# 0101.net
KiCad netlist of a schematic drawn in EAGLE
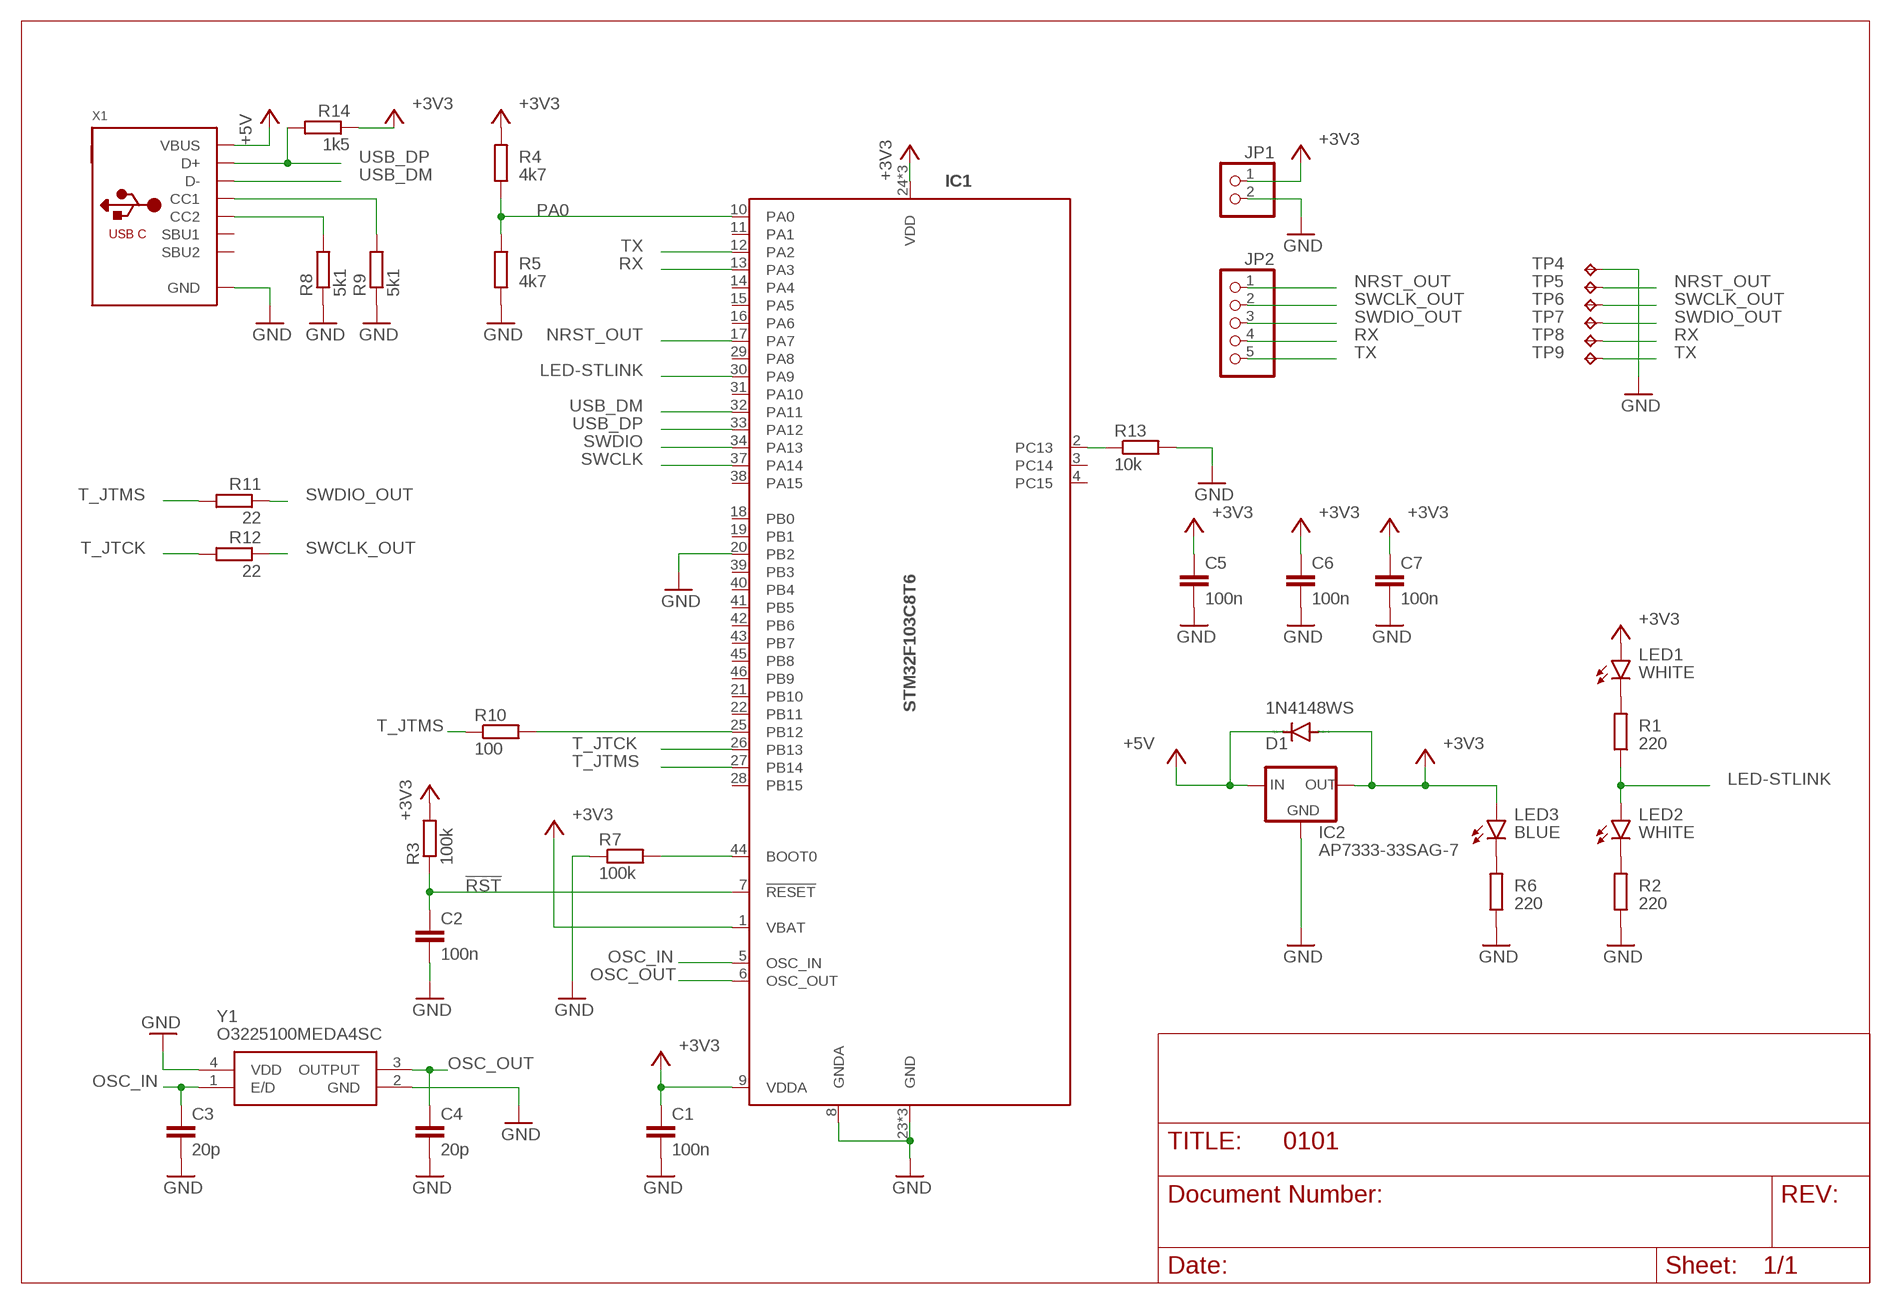
[diagram p0: schematic, sheet 1]

(export (version "E")
  (design (tool "Eeschema 10.0.6"))
  (components
    (comp (ref "C1")
      (value "100n")
      (footprint "eagle-import:C0402")
      (libsource (lib "eagle-import") (part "C-EUC0402"))
    )
    (comp (ref "C2")
      (value "100n")
      (footprint "eagle-import:C0402")
      (libsource (lib "eagle-import") (part "C-EUC0402"))
    )
    (comp (ref "C3")
      (value "20p")
      (footprint "eagle-import:C0402")
      (libsource (lib "eagle-import") (part "C-EUC0402"))
    )
    (comp (ref "C4")
      (value "20p")
      (footprint "eagle-import:C0402")
      (libsource (lib "eagle-import") (part "C-EUC0402"))
    )
    (comp (ref "C5")
      (value "100n")
      (footprint "eagle-import:C0402")
      (libsource (lib "eagle-import") (part "C-EUC0402"))
    )
    (comp (ref "C6")
      (value "100n")
      (footprint "eagle-import:C0402")
      (libsource (lib "eagle-import") (part "C-EUC0402"))
    )
    (comp (ref "C7")
      (value "100n")
      (footprint "eagle-import:C0402")
      (libsource (lib "eagle-import") (part "C-EUC0402"))
    )
    (comp (ref "D1")
      (value "1N4148WS")
      (footprint "eagle-import:SOD323-R")
      (libsource (lib "eagle-import") (part "DIODE-SOD323-R"))
    )
    (comp (ref "IC1")
      (value "STM32F103C8T6")
      (footprint "eagle-import:QFP48-7X7-0.5")
      (fields (field (name "MF") "ST"))
      (libsource (lib "eagle-import") (part "STM32F103CT68"))
    )
    (comp (ref "IC2")
      (value "AP7333-33SAG-7")
      (footprint "eagle-import:SOT23")
      (libsource (lib "eagle-import") (part "XC63FPM"))
    )
    (comp (ref "JP1")
      (value "PINHD-1X2")
      (footprint "eagle-import:1X02")
      (libsource (lib "eagle-import") (part "PINHD-1X2"))
    )
    (comp (ref "JP2")
      (value "PINHD-1X5")
      (footprint "eagle-import:1X05")
      (libsource (lib "eagle-import") (part "PINHD-1X5"))
    )
    (comp (ref "LED1")
      (value "WHITE")
      (footprint "eagle-import:CHIP-LED0603")
      (libsource (lib "eagle-import") (part "LEDCHIP-LED0603"))
    )
    (comp (ref "LED2")
      (value "WHITE")
      (footprint "eagle-import:CHIP-LED0603")
      (libsource (lib "eagle-import") (part "LEDCHIP-LED0603"))
    )
    (comp (ref "LED3")
      (value "BLUE")
      (footprint "eagle-import:CHIP-LED0603")
      (libsource (lib "eagle-import") (part "LEDCHIP-LED0603"))
    )
    (comp (ref "R1")
      (value "220")
      (footprint "eagle-import:R0402")
      (libsource (lib "eagle-import") (part "R-EU_R0402"))
    )
    (comp (ref "R2")
      (value "220")
      (footprint "eagle-import:R0402")
      (libsource (lib "eagle-import") (part "R-EU_R0402"))
    )
    (comp (ref "R3")
      (value "100k")
      (footprint "eagle-import:R0402")
      (libsource (lib "eagle-import") (part "R-EU_R0402"))
    )
    (comp (ref "R4")
      (value "4k7")
      (footprint "eagle-import:R0402")
      (libsource (lib "eagle-import") (part "R-EU_R0402"))
    )
    (comp (ref "R5")
      (value "4k7")
      (footprint "eagle-import:R0402")
      (libsource (lib "eagle-import") (part "R-EU_R0402"))
    )
    (comp (ref "R6")
      (value "220")
      (footprint "eagle-import:R0402")
      (libsource (lib "eagle-import") (part "R-EU_R0402"))
    )
    (comp (ref "R7")
      (value "100k")
      (footprint "eagle-import:R0402")
      (libsource (lib "eagle-import") (part "R-EU_R0402"))
    )
    (comp (ref "R8")
      (value "5k1")
      (footprint "eagle-import:R0402")
      (libsource (lib "eagle-import") (part "R-EU_R0402"))
    )
    (comp (ref "R9")
      (value "5k1")
      (footprint "eagle-import:R0402")
      (libsource (lib "eagle-import") (part "R-EU_R0402"))
    )
    (comp (ref "R10")
      (value "100")
      (footprint "eagle-import:R0402")
      (libsource (lib "eagle-import") (part "R-EU_R0402"))
    )
    (comp (ref "R11")
      (value "22")
      (footprint "eagle-import:R0402")
      (libsource (lib "eagle-import") (part "R-EU_R0402"))
    )
    (comp (ref "R12")
      (value "22")
      (footprint "eagle-import:R0402")
      (libsource (lib "eagle-import") (part "R-EU_R0402"))
    )
    (comp (ref "R13")
      (value "10k")
      (footprint "eagle-import:R0402")
      (libsource (lib "eagle-import") (part "R-EU_R0402"))
    )
    (comp (ref "R14")
      (value "1k5")
      (footprint "eagle-import:R0402")
      (libsource (lib "eagle-import") (part "R-EU_R0402"))
    )
    (comp (ref "TP4")
      (value "TPTP10SQ")
      (footprint "eagle-import:TP10SQ")
      (libsource (lib "eagle-import") (part "TPTP10SQ"))
    )
    (comp (ref "TP5")
      (value "TPTP10R")
      (footprint "eagle-import:TP10R")
      (libsource (lib "eagle-import") (part "TPTP10R"))
    )
    (comp (ref "TP6")
      (value "TPTP10R")
      (footprint "eagle-import:TP10R")
      (libsource (lib "eagle-import") (part "TPTP10R"))
    )
    (comp (ref "TP7")
      (value "TPTP10R")
      (footprint "eagle-import:TP10R")
      (libsource (lib "eagle-import") (part "TPTP10R"))
    )
    (comp (ref "TP8")
      (value "TPTP10R")
      (footprint "eagle-import:TP10R")
      (libsource (lib "eagle-import") (part "TPTP10R"))
    )
    (comp (ref "TP9")
      (value "TPTP10R")
      (footprint "eagle-import:TP10R")
      (libsource (lib "eagle-import") (part "TPTP10R"))
    )
    (comp (ref "X1")
      (value "USB_C")
      (footprint "eagle-import:USB_C_CUSB31-CFM2AX-01-X")
      (libsource (lib "eagle-import") (part "USB_C"))
    )
    (comp (ref "Y1")
      (value "O3225100MEDA4SC")
      (footprint "eagle-import:O3225100MEDA4SC")
      (libsource (lib "eagle-import") (part "O3225100MEDA4SC"))
    )
  )
  (nets
    (net (code "1") (name "+3V3") (class "Default")
      (node (ref "C1") (pin "1") (pinfunction "1_1") (pintype "passive"))
      (node (ref "C5") (pin "1") (pinfunction "1_1") (pintype "passive"))
      (node (ref "C6") (pin "1") (pinfunction "1_1") (pintype "passive"))
      (node (ref "C7") (pin "1") (pinfunction "1_1") (pintype "passive"))
      (node (ref "D1") (pin "A") (pinfunction "A_A") (pintype "passive"))
      (node (ref "IC1") (pin "1") (pinfunction "VBAT_1") (pintype "power_in"))
      (node (ref "IC1") (pin "24") (pinfunction "VDD_24") (pintype "power_in"))
      (node (ref "IC1") (pin "36") (pinfunction "VDD_36") (pintype "power_in"))
      (node (ref "IC1") (pin "48") (pinfunction "VDD_48") (pintype "power_in"))
      (node (ref "IC1") (pin "9") (pinfunction "VDDA_9") (pintype "input"))
      (node (ref "IC2") (pin "2") (pinfunction "OUT_2") (pintype "passive"))
      (node (ref "JP1") (pin "1") (pinfunction "1_1") (pintype "passive"))
      (node (ref "LED1") (pin "A") (pinfunction "A_A") (pintype "passive"))
      (node (ref "LED3") (pin "A") (pinfunction "A_A") (pintype "passive"))
      (node (ref "R14") (pin "1") (pinfunction "1_1") (pintype "passive"))
      (node (ref "R3") (pin "2") (pinfunction "2_2") (pintype "passive"))
      (node (ref "R4") (pin "2") (pinfunction "2_2") (pintype "passive"))
    )
    (net (code "2") (name "+5V") (class "Default")
      (node (ref "D1") (pin "C") (pinfunction "C_C") (pintype "passive"))
      (node (ref "IC2") (pin "3") (pinfunction "IN_3") (pintype "input"))
      (node (ref "X1") (pin "A4B9") (pinfunction "VBUS_A4B9") (pintype "power_in"))
      (node (ref "X1") (pin "B4A9") (pinfunction "VBUS_B4A9") (pintype "power_in"))
    )
    (net (code "3") (name "/LED-STLINK") (class "Default")
      (node (ref "IC1") (pin "30") (pinfunction "PA9_30") (pintype "bidirectional"))
      (node (ref "LED2") (pin "A") (pinfunction "A_A") (pintype "passive"))
      (node (ref "R1") (pin "1") (pinfunction "1_1") (pintype "passive"))
    )
    (net (code "4") (name "/NRST_OUT") (class "Default")
      (node (ref "IC1") (pin "17") (pinfunction "PA7_17") (pintype "bidirectional"))
      (node (ref "JP2") (pin "1") (pinfunction "1_1") (pintype "passive"))
      (node (ref "TP5") (pin "TP") (pinfunction "TP_TP") (pintype "input"))
    )
    (net (code "5") (name "/OSC_IN") (class "Default")
      (node (ref "C3") (pin "1") (pinfunction "1_1") (pintype "passive"))
      (node (ref "IC1") (pin "5") (pinfunction "OSC_IN_5") (pintype "input"))
      (node (ref "Y1") (pin "1") (pinfunction "E/D_1") (pintype "bidirectional"))
    )
    (net (code "6") (name "/OSC_OUT") (class "Default")
      (node (ref "C4") (pin "1") (pinfunction "1_1") (pintype "passive"))
      (node (ref "IC1") (pin "6") (pinfunction "OSC_OUT_6") (pintype "output"))
      (node (ref "Y1") (pin "3") (pinfunction "OUTPUT_3") (pintype "bidirectional"))
    )
    (net (code "7") (name "/PA0") (class "Default")
      (node (ref "IC1") (pin "10") (pinfunction "PA0_10") (pintype "bidirectional"))
      (node (ref "R4") (pin "1") (pinfunction "1_1") (pintype "passive"))
      (node (ref "R5") (pin "2") (pinfunction "2_2") (pintype "passive"))
    )
    (net (code "8") (name "/RX") (class "Default")
      (node (ref "IC1") (pin "13") (pinfunction "PA3_13") (pintype "bidirectional"))
      (node (ref "JP2") (pin "4") (pinfunction "4_4") (pintype "passive"))
      (node (ref "TP8") (pin "TP") (pinfunction "TP_TP") (pintype "input"))
    )
    (net (code "9") (name "/SWCLK") (class "Default")
      (node (ref "IC1") (pin "37") (pinfunction "PA14_37") (pintype "bidirectional"))
    )
    (net (code "10") (name "/SWCLK_OUT") (class "Default")
      (node (ref "JP2") (pin "2") (pinfunction "2_2") (pintype "passive"))
      (node (ref "R12") (pin "1") (pinfunction "1_1") (pintype "passive"))
      (node (ref "TP6") (pin "TP") (pinfunction "TP_TP") (pintype "input"))
    )
    (net (code "11") (name "/SWDIO") (class "Default")
      (node (ref "IC1") (pin "34") (pinfunction "PA13_34") (pintype "bidirectional"))
    )
    (net (code "12") (name "/SWDIO_OUT") (class "Default")
      (node (ref "JP2") (pin "3") (pinfunction "3_3") (pintype "passive"))
      (node (ref "R11") (pin "1") (pinfunction "1_1") (pintype "passive"))
      (node (ref "TP7") (pin "TP") (pinfunction "TP_TP") (pintype "input"))
    )
    (net (code "13") (name "/TX") (class "Default")
      (node (ref "IC1") (pin "12") (pinfunction "PA2_12") (pintype "bidirectional"))
      (node (ref "JP2") (pin "5") (pinfunction "5_5") (pintype "passive"))
      (node (ref "TP9") (pin "TP") (pinfunction "TP_TP") (pintype "input"))
    )
    (net (code "14") (name "/T_JTCK") (class "Default")
      (node (ref "IC1") (pin "26") (pinfunction "PB13_26") (pintype "bidirectional"))
      (node (ref "R12") (pin "2") (pinfunction "2_2") (pintype "passive"))
    )
    (net (code "15") (name "/T_JTMS") (class "Default")
      (node (ref "IC1") (pin "27") (pinfunction "PB14_27") (pintype "bidirectional"))
      (node (ref "R10") (pin "1") (pinfunction "1_1") (pintype "passive"))
      (node (ref "R11") (pin "2") (pinfunction "2_2") (pintype "passive"))
    )
    (net (code "16") (name "/USB_DM") (class "Default")
      (node (ref "IC1") (pin "32") (pinfunction "PA11_32") (pintype "bidirectional"))
      (node (ref "X1") (pin "A7") (pinfunction "D-_A7") (pintype "bidirectional"))
      (node (ref "X1") (pin "B7") (pinfunction "D-_B7") (pintype "bidirectional"))
    )
    (net (code "17") (name "/USB_DP") (class "Default")
      (node (ref "IC1") (pin "33") (pinfunction "PA12_33") (pintype "bidirectional"))
      (node (ref "R14") (pin "2") (pinfunction "2_2") (pintype "passive"))
      (node (ref "X1") (pin "A6") (pinfunction "D+_A6") (pintype "bidirectional"))
      (node (ref "X1") (pin "B6") (pinfunction "D+_B6") (pintype "bidirectional"))
    )
    (net (code "18") (name "/~{RST}") (class "Default")
      (node (ref "C2") (pin "1") (pinfunction "1_1") (pintype "passive"))
      (node (ref "IC1") (pin "7") (pinfunction "~{RESET}_7") (pintype "input"))
      (node (ref "R3") (pin "1") (pinfunction "1_1") (pintype "passive"))
    )
    (net (code "19") (name "GND") (class "Default")
      (node (ref "C1") (pin "2") (pinfunction "2_2") (pintype "passive"))
      (node (ref "C2") (pin "2") (pinfunction "2_2") (pintype "passive"))
      (node (ref "C3") (pin "2") (pinfunction "2_2") (pintype "passive"))
      (node (ref "C4") (pin "2") (pinfunction "2_2") (pintype "passive"))
      (node (ref "C5") (pin "2") (pinfunction "2_2") (pintype "passive"))
      (node (ref "C6") (pin "2") (pinfunction "2_2") (pintype "passive"))
      (node (ref "C7") (pin "2") (pinfunction "2_2") (pintype "passive"))
      (node (ref "IC1") (pin "20") (pinfunction "PB2_20") (pintype "bidirectional"))
      (node (ref "IC1") (pin "23") (pinfunction "GND_23") (pintype "power_in"))
      (node (ref "IC1") (pin "35") (pinfunction "GND_35") (pintype "power_in"))
      (node (ref "IC1") (pin "47") (pinfunction "GND_47") (pintype "power_in"))
      (node (ref "IC1") (pin "8") (pinfunction "GNDA_8") (pintype "bidirectional"))
      (node (ref "IC2") (pin "1") (pinfunction "GND_1") (pintype "input"))
      (node (ref "JP1") (pin "2") (pinfunction "2_2") (pintype "passive"))
      (node (ref "R13") (pin "2") (pinfunction "2_2") (pintype "passive"))
      (node (ref "R2") (pin "1") (pinfunction "1_1") (pintype "passive"))
      (node (ref "R5") (pin "1") (pinfunction "1_1") (pintype "passive"))
      (node (ref "R6") (pin "1") (pinfunction "1_1") (pintype "passive"))
      (node (ref "R7") (pin "1") (pinfunction "1_1") (pintype "passive"))
      (node (ref "R8") (pin "1") (pinfunction "1_1") (pintype "passive"))
      (node (ref "R9") (pin "1") (pinfunction "1_1") (pintype "passive"))
      (node (ref "TP4") (pin "TP") (pinfunction "TP_TP") (pintype "input"))
      (node (ref "X1") (pin "A1B12") (pinfunction "GND_A1B12") (pintype "power_in"))
      (node (ref "X1") (pin "B1A12") (pinfunction "GND_B1A12") (pintype "power_in"))
      (node (ref "Y1") (pin "2") (pinfunction "GND_2") (pintype "bidirectional"))
      (node (ref "Y1") (pin "4") (pinfunction "VDD_4") (pintype "bidirectional"))
    )
    (net (code "20") (name "Net-(IC1-BOOT0)") (class "Default")
      (node (ref "IC1") (pin "44") (pinfunction "BOOT0_44") (pintype "input"))
      (node (ref "R7") (pin "2") (pinfunction "2_2") (pintype "passive"))
    )
    (net (code "21") (name "Net-(IC1-PB12)") (class "Default")
      (node (ref "IC1") (pin "25") (pinfunction "PB12_25") (pintype "bidirectional"))
      (node (ref "R10") (pin "2") (pinfunction "2_2") (pintype "passive"))
    )
    (net (code "22") (name "Net-(IC1-PC13)") (class "Default")
      (node (ref "IC1") (pin "2") (pinfunction "PC13_2") (pintype "bidirectional"))
      (node (ref "R13") (pin "1") (pinfunction "1_1") (pintype "passive"))
    )
    (net (code "23") (name "Net-(LED1-PadC)") (class "Default")
      (node (ref "LED1") (pin "C") (pinfunction "C_C") (pintype "passive"))
      (node (ref "R1") (pin "2") (pinfunction "2_2") (pintype "passive"))
    )
    (net (code "24") (name "Net-(LED2-PadC)") (class "Default")
      (node (ref "LED2") (pin "C") (pinfunction "C_C") (pintype "passive"))
      (node (ref "R2") (pin "2") (pinfunction "2_2") (pintype "passive"))
    )
    (net (code "25") (name "Net-(LED3-PadC)") (class "Default")
      (node (ref "LED3") (pin "C") (pinfunction "C_C") (pintype "passive"))
      (node (ref "R6") (pin "2") (pinfunction "2_2") (pintype "passive"))
    )
    (net (code "26") (name "Net-(X1-CC1)") (class "Default")
      (node (ref "R9") (pin "2") (pinfunction "2_2") (pintype "passive"))
      (node (ref "X1") (pin "A5") (pinfunction "CC1_A5") (pintype "bidirectional"))
    )
    (net (code "27") (name "Net-(X1-CC2)") (class "Default")
      (node (ref "R8") (pin "2") (pinfunction "2_2") (pintype "passive"))
      (node (ref "X1") (pin "B5") (pinfunction "CC2_B5") (pintype "bidirectional"))
    )
    (net (code "28") (name "unconnected-(IC1-PA1-Pad11)") (class "Default")
      (node (ref "IC1") (pin "11") (pinfunction "PA1_11") (pintype "bidirectional"))
    )
    (net (code "29") (name "unconnected-(IC1-PA4-Pad14)") (class "Default")
      (node (ref "IC1") (pin "14") (pinfunction "PA4_14") (pintype "bidirectional"))
    )
    (net (code "30") (name "unconnected-(IC1-PA5-Pad15)") (class "Default")
      (node (ref "IC1") (pin "15") (pinfunction "PA5_15") (pintype "bidirectional"))
    )
    (net (code "31") (name "unconnected-(IC1-PA6-Pad16)") (class "Default")
      (node (ref "IC1") (pin "16") (pinfunction "PA6_16") (pintype "bidirectional"))
    )
    (net (code "32") (name "unconnected-(IC1-PA8-Pad29)") (class "Default")
      (node (ref "IC1") (pin "29") (pinfunction "PA8_29") (pintype "bidirectional"))
    )
    (net (code "33") (name "unconnected-(IC1-PA10-Pad31)") (class "Default")
      (node (ref "IC1") (pin "31") (pinfunction "PA10_31") (pintype "bidirectional"))
    )
    (net (code "34") (name "unconnected-(IC1-PA15-Pad38)") (class "Default")
      (node (ref "IC1") (pin "38") (pinfunction "PA15_38") (pintype "bidirectional"))
    )
    (net (code "35") (name "unconnected-(IC1-PB0-Pad18)") (class "Default")
      (node (ref "IC1") (pin "18") (pinfunction "PB0_18") (pintype "bidirectional"))
    )
    (net (code "36") (name "unconnected-(IC1-PB1-Pad19)") (class "Default")
      (node (ref "IC1") (pin "19") (pinfunction "PB1_19") (pintype "bidirectional"))
    )
    (net (code "37") (name "unconnected-(IC1-PB3-Pad39)") (class "Default")
      (node (ref "IC1") (pin "39") (pinfunction "PB3_39") (pintype "bidirectional"))
    )
    (net (code "38") (name "unconnected-(IC1-PB4-Pad40)") (class "Default")
      (node (ref "IC1") (pin "40") (pinfunction "PB4_40") (pintype "bidirectional"))
    )
    (net (code "39") (name "unconnected-(IC1-PB5-Pad41)") (class "Default")
      (node (ref "IC1") (pin "41") (pinfunction "PB5_41") (pintype "bidirectional"))
    )
    (net (code "40") (name "unconnected-(IC1-PB6-Pad42)") (class "Default")
      (node (ref "IC1") (pin "42") (pinfunction "PB6_42") (pintype "bidirectional"))
    )
    (net (code "41") (name "unconnected-(IC1-PB7-Pad43)") (class "Default")
      (node (ref "IC1") (pin "43") (pinfunction "PB7_43") (pintype "bidirectional"))
    )
    (net (code "42") (name "unconnected-(IC1-PB8-Pad45)") (class "Default")
      (node (ref "IC1") (pin "45") (pinfunction "PB8_45") (pintype "bidirectional"))
    )
    (net (code "43") (name "unconnected-(IC1-PB9-Pad46)") (class "Default")
      (node (ref "IC1") (pin "46") (pinfunction "PB9_46") (pintype "bidirectional"))
    )
    (net (code "44") (name "unconnected-(IC1-PB10-Pad21)") (class "Default")
      (node (ref "IC1") (pin "21") (pinfunction "PB10_21") (pintype "bidirectional"))
    )
    (net (code "45") (name "unconnected-(IC1-PB11-Pad22)") (class "Default")
      (node (ref "IC1") (pin "22") (pinfunction "PB11_22") (pintype "bidirectional"))
    )
    (net (code "46") (name "unconnected-(IC1-PB15-Pad28)") (class "Default")
      (node (ref "IC1") (pin "28") (pinfunction "PB15_28") (pintype "bidirectional"))
    )
    (net (code "47") (name "unconnected-(IC1-PC14-Pad3)") (class "Default")
      (node (ref "IC1") (pin "3") (pinfunction "PC14_3") (pintype "bidirectional"))
    )
    (net (code "48") (name "unconnected-(IC1-PC15-Pad4)") (class "Default")
      (node (ref "IC1") (pin "4") (pinfunction "PC15_4") (pintype "bidirectional"))
    )
    (net (code "49") (name "unconnected-(X1-SBU1-PadA8)") (class "Default")
      (node (ref "X1") (pin "A8") (pinfunction "SBU1_A8") (pintype "bidirectional"))
    )
    (net (code "50") (name "unconnected-(X1-SBU2-PadB8)") (class "Default")
      (node (ref "X1") (pin "B8") (pinfunction "SBU2_B8") (pintype "bidirectional"))
    )
  )
)
